# 3.net
KiCad netlist of a schematic drawn in Altium Designer
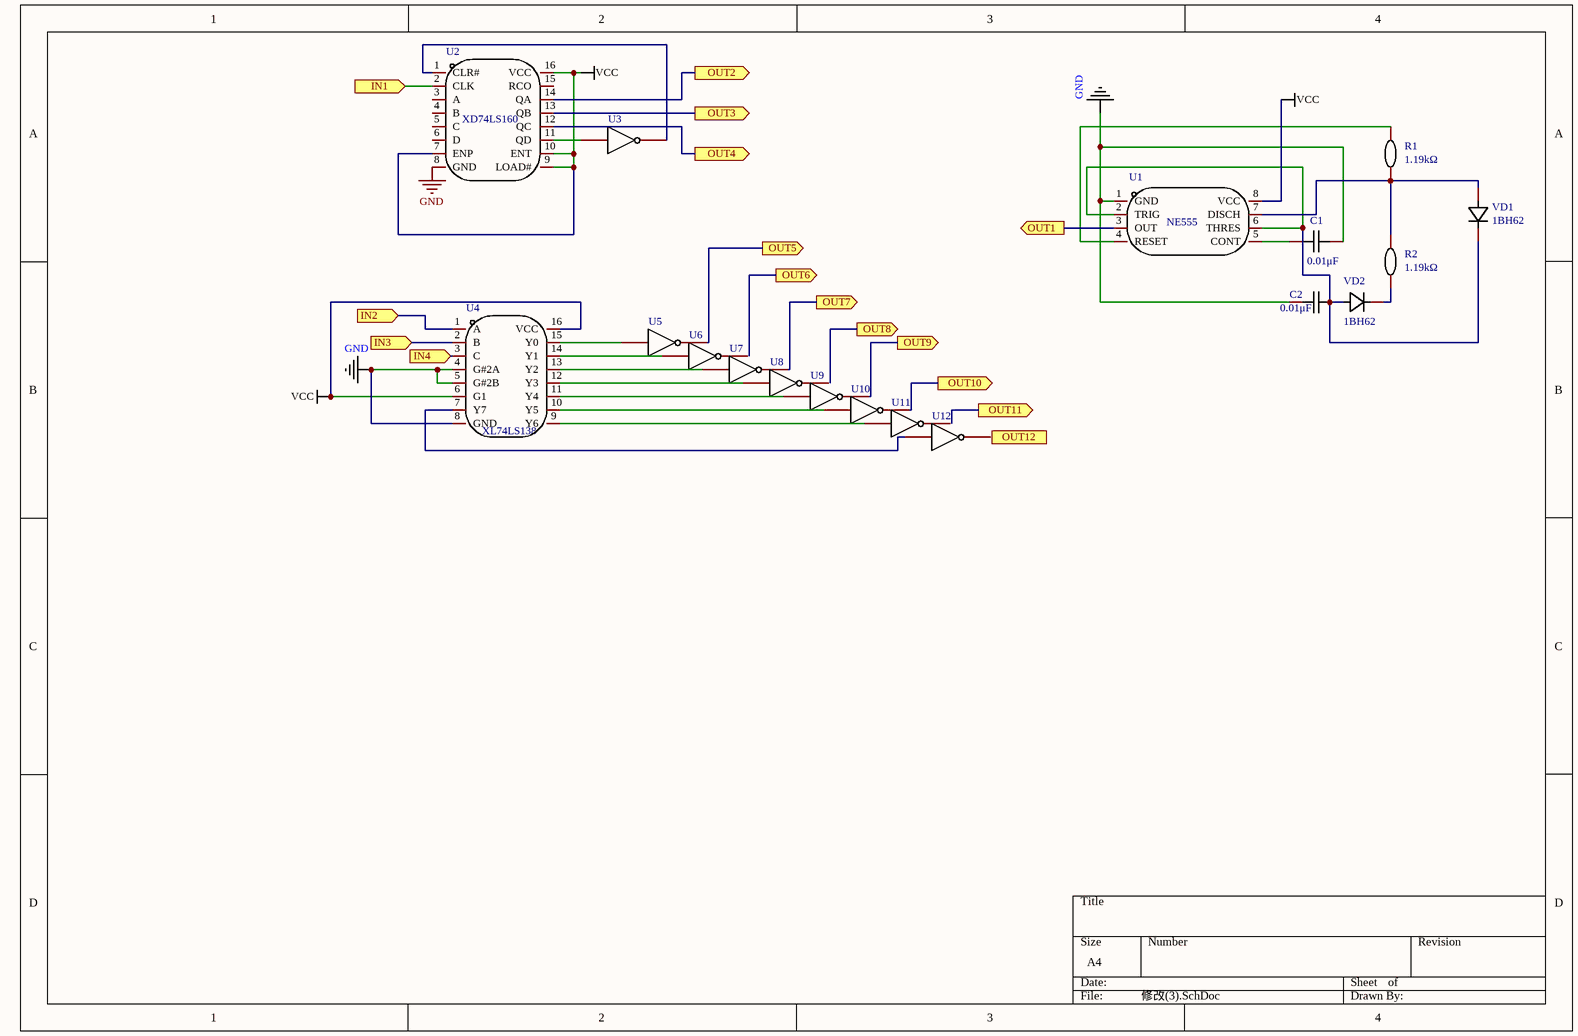
[diagram p0: 修改(3).SchDoc]

(export (version "E")
  (design (tool "Eeschema 10.0.6"))
  (components
    (comp (ref "C1")
      (value "100nF")
      (footprint "C0603")
      (fields (field (name "NAME") "0.01μF"))
      (libsource (lib "altium-import") (part "root_0_CAP_0603_"))
    )
    (comp (ref "C2")
      (value "100nF")
      (footprint "C0603")
      (fields (field (name "NAME") "0.01μF"))
      (libsource (lib "altium-import") (part "root_0_CAP_0603_"))
    )
    (comp (ref "R1")
      (value "10K")
      (footprint "R0603")
      (fields (field (name "NAME") "1.19kΩ"))
      (libsource (lib "altium-import") (part "root_1_Res_0603_"))
    )
    (comp (ref "R2")
      (value "10K")
      (footprint "R0603")
      (fields (field (name "NAME") "1.19kΩ"))
      (libsource (lib "altium-import") (part "root_1_Res_0603_"))
    )
    (comp (ref "U1")
      (value "-")
      (footprint "SOIC-8_L4.9-W3.9-P1.27-LS6.0-BL")
      (description "频率:-;重置时间:-;是否可编程:-;")
      (fields (field (name "MANUFACTURER") "IDCHIP(英锐芯)") (field (name "MANUFACTURER PART") "NE555"))
      (libsource (lib "altium-import") (part "root_0_NE555_C5125085_"))
    )
    (comp (ref "U2")
      (value "XD74LS160")
      (footprint "DIP-16_L19.8-W6.5-P2.54-LS7.6-BL")
      (description "逻辑电路 计数器/分频器")
      (fields (field (name "NAME") "XD74LS160") (field (name "MANUFACTURER") "XINLUDA(信路达)"))
      (libsource (lib "altium-import") (part "root_0_XD74LS160_"))
    )
    (comp (ref "U3") (value "反相器") (libsource (lib "altium-import") (part "root_0_反相器_")))
    (comp (ref "U4")
      (value "XL74LS138")
      (footprint "SOP-16_L9.9-W3.9-P1.27-LS6.1-BL")
      (description "解码器/多路解器 低电平输出电流(IOL)：8mA 高电平输出电流(IOH)：400uA 供电电源：单电源 供电电压：4.75V~5.25V 3 线路到 8 线路解码器/多路解复用器")
      (fields (field (name "NAME") "XL74LS138") (field (name "MANUFACTURER") "XINLUDA(信路达)"))
      (libsource (lib "altium-import") (part "root_0_XL74LS138_"))
    )
    (comp (ref "U5") (value "反相器") (libsource (lib "altium-import") (part "root_0_反相器_")))
    (comp (ref "U6") (value "反相器") (libsource (lib "altium-import") (part "root_0_反相器_")))
    (comp (ref "U7") (value "反相器") (libsource (lib "altium-import") (part "root_0_反相器_")))
    (comp (ref "U8") (value "反相器") (libsource (lib "altium-import") (part "root_0_反相器_")))
    (comp (ref "U9") (value "反相器") (libsource (lib "altium-import") (part "root_0_反相器_")))
    (comp (ref "U10") (value "反相器") (libsource (lib "altium-import") (part "root_0_反相器_")))
    (comp (ref "U11") (value "反相器") (libsource (lib "altium-import") (part "root_0_反相器_")))
    (comp (ref "U12") (value "反相器") (libsource (lib "altium-import") (part "root_0_反相器_")))
    (comp (ref "VD1")
      (value "1N4007")
      (footprint "SMA_L4.3-W2.6-LS5.1-RD")
      (fields (field (name "NAME") "1BH62"))
      (libsource (lib "altium-import") (part "root_1_1N4007_"))
    )
    (comp (ref "VD2")
      (value "1N4007")
      (footprint "SMA_L4.3-W2.6-LS5.1-RD")
      (fields (field (name "NAME") "1BH62"))
      (libsource (lib "altium-import") (part "root_2_1N4007_"))
    )
  )
  (nets
    (net (code "1") (name "/IN1") (class "Default")
      (node (ref "U2") (pin "2") (pinfunction "CLK_2") (pintype "passive"))
    )
    (net (code "2") (name "/IN2") (class "Default")
      (node (ref "U4") (pin "1") (pinfunction "A_1") (pintype "passive"))
    )
    (net (code "3") (name "/IN3") (class "Default")
      (node (ref "U4") (pin "2") (pinfunction "B_2") (pintype "passive"))
    )
    (net (code "4") (name "/IN4") (class "Default")
      (node (ref "U4") (pin "3") (pinfunction "C_3") (pintype "passive"))
    )
    (net (code "5") (name "/OUT1") (class "Default")
      (node (ref "U1") (pin "3") (pinfunction "OUT_3") (pintype "passive"))
    )
    (net (code "6") (name "/OUT2") (class "Default")
      (node (ref "U2") (pin "14") (pinfunction "QA_14") (pintype "passive"))
    )
    (net (code "7") (name "/OUT3") (class "Default")
      (node (ref "U2") (pin "13") (pinfunction "QB_13") (pintype "passive"))
    )
    (net (code "8") (name "/OUT4") (class "Default")
      (node (ref "U2") (pin "12") (pinfunction "QC_12") (pintype "passive"))
    )
    (net (code "9") (name "/OUT5") (class "Default")
      (node (ref "U5") (pin "2") (pinfunction "2_2") (pintype "passive"))
    )
    (net (code "11") (name "/OUT7") (class "Default")
      (node (ref "U7") (pin "2") (pinfunction "2_2") (pintype "passive"))
    )
    (net (code "13") (name "/OUT9") (class "Default")
      (node (ref "U9") (pin "2") (pinfunction "2_2") (pintype "passive"))
    )
    (net (code "14") (name "/OUT10") (class "Default")
      (node (ref "U10") (pin "2") (pinfunction "2_2") (pintype "passive"))
    )
    (net (code "17") (name "<NO NET>") (class "Default")
      (node (ref "C1") (pin "2") (pinfunction "2_2") (pintype "passive"))
      (node (ref "C2") (pin "1") (pinfunction "1_1") (pintype "passive"))
      (node (ref "U1") (pin "1") (pinfunction "GND_1") (pintype "passive"))
      (node (ref "U4") (pin "4") (pinfunction "G#2A_4") (pintype "passive"))
      (node (ref "U4") (pin "5") (pinfunction "G#2B_5") (pintype "passive"))
      (node (ref "U4") (pin "8") (pinfunction "GND_8") (pintype "passive"))
    )
    (net (code "18") (name "GND") (class "Default")
      (node (ref "U2") (pin "8") (pinfunction "GND_8") (pintype "passive"))
    )
    (net (code "19") (name "Net-(U1-CONT)") (class "Default")
      (node (ref "C1") (pin "1") (pinfunction "1_1") (pintype "passive"))
      (node (ref "U1") (pin "5") (pinfunction "CONT_5") (pintype "passive"))
    )
    (net (code "20") (name "Net-(U1-DISCH)") (class "Default")
      (node (ref "R1") (pin "1") (pinfunction "1_1") (pintype "passive"))
      (node (ref "R2") (pin "2") (pinfunction "2_2") (pintype "passive"))
      (node (ref "U1") (pin "7") (pinfunction "DISCH_7") (pintype "passive"))
      (node (ref "VD1") (pin "2") (pinfunction "A_2") (pintype "passive"))
    )
    (net (code "21") (name "Net-(U1-RESET)") (class "Default")
      (node (ref "R1") (pin "2") (pinfunction "2_2") (pintype "passive"))
      (node (ref "U1") (pin "4") (pinfunction "RESET_4") (pintype "passive"))
    )
    (net (code "22") (name "Net-(U1-THRES)") (class "Default")
      (node (ref "C2") (pin "2") (pinfunction "2_2") (pintype "passive"))
      (node (ref "U1") (pin "2") (pinfunction "TRIG_2") (pintype "passive"))
      (node (ref "U1") (pin "6") (pinfunction "THRES_6") (pintype "passive"))
      (node (ref "VD1") (pin "1") (pinfunction "K_1") (pintype "passive"))
      (node (ref "VD2") (pin "2") (pinfunction "A_2") (pintype "passive"))
    )
    (net (code "23") (name "Net-(U2-CLR#)") (class "Default")
      (node (ref "U2") (pin "1") (pinfunction "CLR#_1") (pintype "passive"))
      (node (ref "U3") (pin "2") (pinfunction "2_2") (pintype "passive"))
    )
    (net (code "24") (name "Net-(U2-QD)") (class "Default")
      (node (ref "U2") (pin "11") (pinfunction "QD_11") (pintype "passive"))
      (node (ref "U3") (pin "1") (pinfunction "1_1") (pintype "passive"))
    )
    (net (code "25") (name "Net-(U4-Y0)") (class "Default")
      (node (ref "U4") (pin "15") (pinfunction "Y0_15") (pintype "passive"))
      (node (ref "U5") (pin "1") (pinfunction "1_1") (pintype "passive"))
    )
    (net (code "26") (name "Net-(U4-Y1)") (class "Default")
      (node (ref "U4") (pin "14") (pinfunction "Y1_14") (pintype "passive"))
      (node (ref "U6") (pin "1") (pinfunction "1_1") (pintype "passive"))
    )
    (net (code "27") (name "Net-(U4-Y2)") (class "Default")
      (node (ref "U4") (pin "13") (pinfunction "Y2_13") (pintype "passive"))
      (node (ref "U7") (pin "1") (pinfunction "1_1") (pintype "passive"))
    )
    (net (code "28") (name "Net-(U4-Y3)") (class "Default")
      (node (ref "U4") (pin "12") (pinfunction "Y3_12") (pintype "passive"))
      (node (ref "U8") (pin "1") (pinfunction "1_1") (pintype "passive"))
    )
    (net (code "29") (name "Net-(U4-Y4)") (class "Default")
      (node (ref "U4") (pin "11") (pinfunction "Y4_11") (pintype "passive"))
      (node (ref "U9") (pin "1") (pinfunction "1_1") (pintype "passive"))
    )
    (net (code "30") (name "Net-(U4-Y5)") (class "Default")
      (node (ref "U10") (pin "1") (pinfunction "1_1") (pintype "passive"))
      (node (ref "U4") (pin "10") (pinfunction "Y5_10") (pintype "passive"))
    )
    (net (code "31") (name "Net-(U4-Y6)") (class "Default")
      (node (ref "U11") (pin "1") (pinfunction "1_1") (pintype "passive"))
      (node (ref "U4") (pin "9") (pinfunction "Y6_9") (pintype "passive"))
    )
    (net (code "32") (name "Net-(U4-Y7)") (class "Default")
      (node (ref "U12") (pin "1") (pinfunction "1_1") (pintype "passive"))
      (node (ref "U4") (pin "7") (pinfunction "Y7_7") (pintype "passive"))
    )
    (net (code "33") (name "Net-(VD2-K)") (class "Default")
      (node (ref "R2") (pin "1") (pinfunction "1_1") (pintype "passive"))
      (node (ref "VD2") (pin "1") (pinfunction "K_1") (pintype "passive"))
    )
    (net (code "34") (name "VCC") (class "Default")
      (node (ref "U1") (pin "8") (pinfunction "VCC_8") (pintype "passive"))
      (node (ref "U2") (pin "10") (pinfunction "ENT_10") (pintype "passive"))
      (node (ref "U2") (pin "16") (pinfunction "VCC_16") (pintype "passive"))
      (node (ref "U2") (pin "7") (pinfunction "ENP_7") (pintype "passive"))
      (node (ref "U2") (pin "9") (pinfunction "LOAD#_9") (pintype "passive"))
      (node (ref "U4") (pin "16") (pinfunction "VCC_16") (pintype "passive"))
      (node (ref "U4") (pin "6") (pinfunction "G1_6") (pintype "passive"))
    )
    (net (code "35") (name "unconnected-(U2-A-Pad3)") (class "Default")
      (node (ref "U2") (pin "3") (pinfunction "A_3") (pintype "passive"))
    )
    (net (code "36") (name "unconnected-(U2-B-Pad4)") (class "Default")
      (node (ref "U2") (pin "4") (pinfunction "B_4") (pintype "passive"))
    )
    (net (code "37") (name "unconnected-(U2-C-Pad5)") (class "Default")
      (node (ref "U2") (pin "5") (pinfunction "C_5") (pintype "passive"))
    )
    (net (code "38") (name "unconnected-(U2-D-Pad6)") (class "Default")
      (node (ref "U2") (pin "6") (pinfunction "D_6") (pintype "passive"))
    )
    (net (code "39") (name "unconnected-(U2-RCO-Pad15)") (class "Default")
      (node (ref "U2") (pin "15") (pinfunction "RCO_15") (pintype "passive"))
    )
    (net (code "40") (name "unconnected-(U6-Pad2)") (class "Default")
      (node (ref "U6") (pin "2") (pinfunction "2_2") (pintype "passive"))
    )
    (net (code "41") (name "unconnected-(U8-Pad2)") (class "Default")
      (node (ref "U8") (pin "2") (pinfunction "2_2") (pintype "passive"))
    )
    (net (code "42") (name "unconnected-(U11-Pad2)") (class "Default")
      (node (ref "U11") (pin "2") (pinfunction "2_2") (pintype "passive"))
    )
    (net (code "43") (name "unconnected-(U12-Pad2)") (class "Default")
      (node (ref "U12") (pin "2") (pinfunction "2_2") (pintype "passive"))
    )
  )
)
